# TinyISD1700_V2_2020-08-19-smd-sop-SPI-12.net
KiCad netlist of a schematic drawn in EAGLE
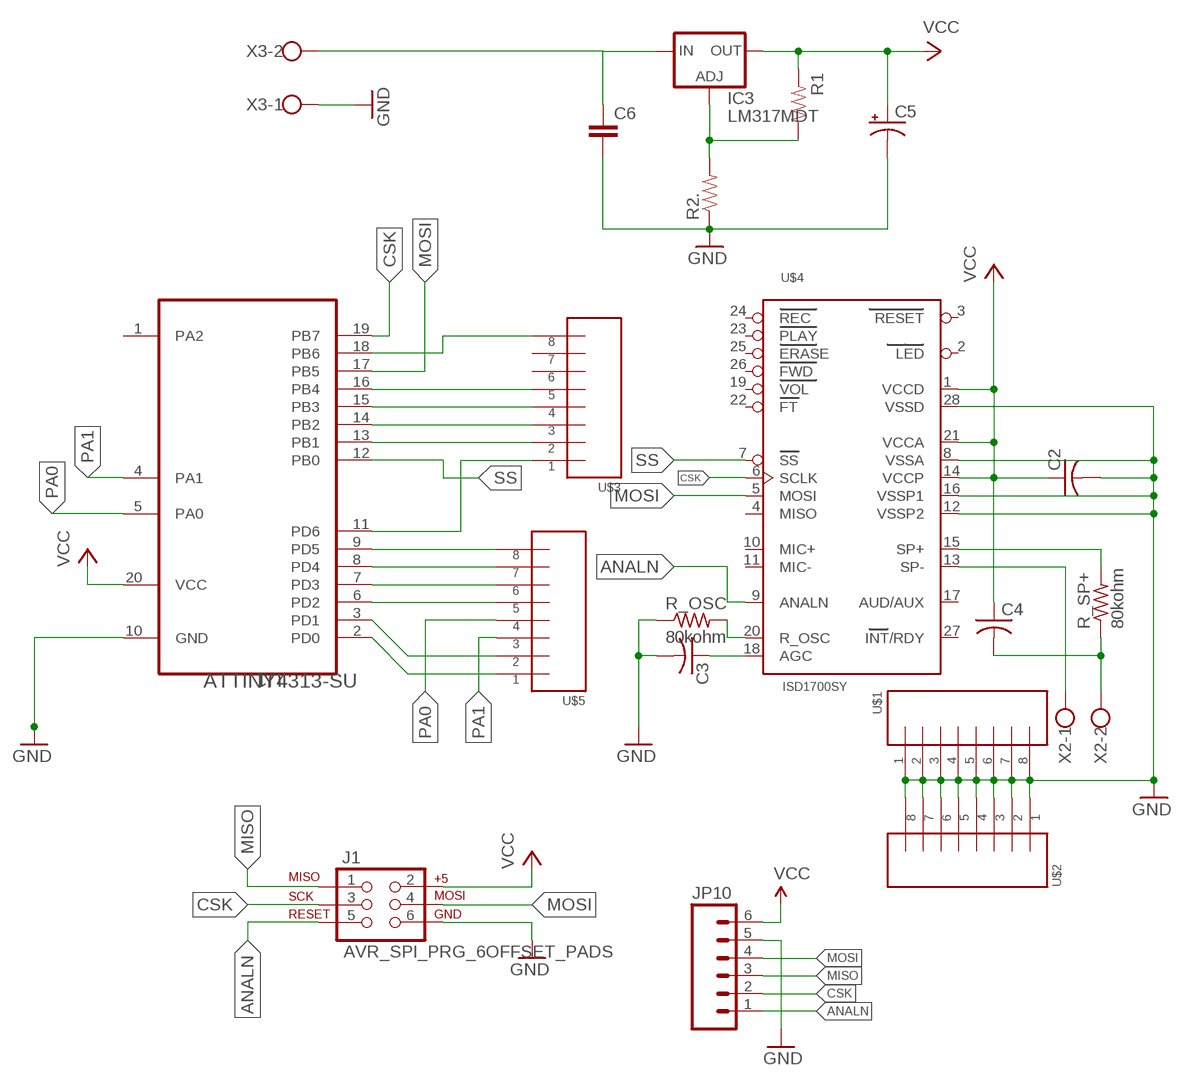
[diagram p0: schematic, sheet 1]

(export (version "E")
  (design (tool "Eeschema 10.0.6"))
  (components
    (comp (ref "C2")
      (value "C-US050-030X075")
      (footprint "eagle-import:C050-030X075")
      (libsource (lib "eagle-import") (part "C-US050-030X075"))
    )
    (comp (ref "C3")
      (value "C-US050-030X075")
      (footprint "eagle-import:C050-030X075")
      (libsource (lib "eagle-import") (part "C-US050-030X075"))
    )
    (comp (ref "C4")
      (value "C-US050-030X075")
      (footprint "eagle-import:C050-030X075")
      (libsource (lib "eagle-import") (part "C-US050-030X075"))
    )
    (comp (ref "C5")
      (value "CAP_POL1206")
      (footprint "eagle-import:EIA3216")
      (libsource (lib "eagle-import") (part "CAP_POL1206"))
    )
    (comp (ref "C6")
      (value "CAP0805")
      (footprint "eagle-import:0805")
      (libsource (lib "eagle-import") (part "CAP0805"))
    )
    (comp (ref "IC3")
      (value "LM317MDT")
      (footprint "eagle-import:DPACK")
      (libsource (lib "eagle-import") (part "LM317?MDT"))
    )
    (comp (ref "J1")
      (value "AVR_SPI_PRG_6OFFSET_PADS")
      (footprint "eagle-import:2X3_OFFSET")
      (libsource (lib "eagle-import") (part "AVR_SPI_PRG_6OFFSET_PADS"))
    )
    (comp (ref "JP10")
      (value "M06SIP")
      (footprint "eagle-import:1X06")
      (libsource (lib "eagle-import") (part "M06SIP"))
    )
    (comp (ref "R1")
      (value "RESISTOR")
      (footprint "eagle-import:0805")
      (libsource (lib "eagle-import") (part "RESISTOR"))
    )
    (comp (ref "R2.")
      (value "RESISTOR")
      (footprint "eagle-import:0805")
      (libsource (lib "eagle-import") (part "RESISTOR"))
    )
    (comp (ref "R_OSC")
      (value "80kohm")
      (footprint "eagle-import:0204V")
      (libsource (lib "eagle-import") (part "R-US_0204/2V"))
    )
    (comp (ref "R_SP+")
      (value "80kohm")
      (footprint "eagle-import:0204V")
      (libsource (lib "eagle-import") (part "R-US_0204/2V"))
    )
    (comp (ref "U$1")
      (value "8PIN_HEADER")
      (footprint "eagle-import:8PIN_HEADER")
      (fields (field (name "MF") "RENESAS") (field (name "MPN") "YSDKS128E10"))
      (libsource (lib "eagle-import") (part "8PIN_HEADER"))
    )
    (comp (ref "U$2")
      (value "8PIN_HEADER")
      (footprint "eagle-import:8PIN_HEADER")
      (fields (field (name "MF") "RENESAS") (field (name "MPN") "YSDKS128E10"))
      (libsource (lib "eagle-import") (part "8PIN_HEADER"))
    )
    (comp (ref "U$3")
      (value "8PIN_HEADER")
      (footprint "eagle-import:8PIN_HEADER")
      (fields (field (name "MF") "RENESAS") (field (name "MPN") "YSDKS128E10"))
      (libsource (lib "eagle-import") (part "8PIN_HEADER"))
    )
    (comp (ref "U$4")
      (value "ISD1700SY")
      (footprint "eagle-import:SO28W")
      (libsource (lib "eagle-import") (part "ISD1700SY"))
    )
    (comp (ref "U$5")
      (value "8PIN_HEADER")
      (footprint "eagle-import:8PIN_HEADER")
      (fields (field (name "MF") "RENESAS") (field (name "MPN") "YSDKS128E10"))
      (libsource (lib "eagle-import") (part "8PIN_HEADER"))
    )
    (comp (ref "U1")
      (value "ATTINY4313-SU")
      (footprint "eagle-import:SOIC127P1032X265-20N")
      (fields (field (name "MF") "MICROCHIP"))
      (libsource (lib "eagle-import") (part "ATTINY4313-SU"))
    )
    (comp (ref "X2")
      (value "W237-102")
      (footprint "eagle-import:W237-102")
      (fields (field (name "MPN") "237-102"))
      (libsource (lib "eagle-import") (part "W237-102"))
    )
    (comp (ref "X3")
      (value "W237-102")
      (footprint "eagle-import:W237-102")
      (fields (field (name "MPN") "237-102") (field (name "OC_NEWARK") "70K9898"))
      (libsource (lib "eagle-import") (part "W237-102"))
    )
  )
  (nets
    (net (code "1") (name "ANALN") (class "Default")
      (node (ref "J1") (pin "5") (pinfunction "5_5") (pintype "passive"))
      (node (ref "JP10") (pin "1") (pinfunction "1_1") (pintype "passive"))
      (node (ref "U$4") (pin "9") (pinfunction "ANALN_9") (pintype "input"))
    )
    (net (code "2") (name "CSK") (class "Default")
      (node (ref "J1") (pin "3") (pinfunction "3_3") (pintype "passive"))
      (node (ref "JP10") (pin "2") (pinfunction "2_2") (pintype "passive"))
      (node (ref "U$4") (pin "6") (pinfunction "SCLK_6") (pintype "input"))
      (node (ref "U1") (pin "19") (pinfunction "PB7_19") (pintype "bidirectional"))
    )
    (net (code "3") (name "GND") (class "Default")
      (node (ref "C2") (pin "2") (pinfunction "2_2") (pintype "passive"))
      (node (ref "C3") (pin "2") (pinfunction "2_2") (pintype "passive"))
      (node (ref "C5") (pin "C") (pinfunction "-_C") (pintype "passive"))
      (node (ref "C6") (pin "2") (pinfunction "2_2") (pintype "passive"))
      (node (ref "J1") (pin "6") (pinfunction "6_6") (pintype "passive"))
      (node (ref "JP10") (pin "5") (pinfunction "5_5") (pintype "passive"))
      (node (ref "R2.") (pin "1") (pinfunction "1_1") (pintype "passive"))
      (node (ref "R_OSC") (pin "1") (pinfunction "1_1") (pintype "passive"))
      (node (ref "U$1") (pin "P$1") (pinfunction "P$1_P$1") (pintype "bidirectional"))
      (node (ref "U$1") (pin "P$2") (pinfunction "P$2_P$2") (pintype "bidirectional"))
      (node (ref "U$1") (pin "P$3") (pinfunction "P$3_P$3") (pintype "bidirectional"))
      (node (ref "U$1") (pin "P$4") (pinfunction "P$4_P$4") (pintype "bidirectional"))
      (node (ref "U$1") (pin "P$5") (pinfunction "P$5_P$5") (pintype "bidirectional"))
      (node (ref "U$1") (pin "P$6") (pinfunction "P$6_P$6") (pintype "bidirectional"))
      (node (ref "U$1") (pin "P$7") (pinfunction "P$7_P$7") (pintype "bidirectional"))
      (node (ref "U$1") (pin "P$8") (pinfunction "P$8_P$8") (pintype "bidirectional"))
      (node (ref "U$2") (pin "P$1") (pinfunction "P$1_P$1") (pintype "bidirectional"))
      (node (ref "U$2") (pin "P$2") (pinfunction "P$2_P$2") (pintype "bidirectional"))
      (node (ref "U$2") (pin "P$3") (pinfunction "P$3_P$3") (pintype "bidirectional"))
      (node (ref "U$2") (pin "P$4") (pinfunction "P$4_P$4") (pintype "bidirectional"))
      (node (ref "U$2") (pin "P$5") (pinfunction "P$5_P$5") (pintype "bidirectional"))
      (node (ref "U$2") (pin "P$6") (pinfunction "P$6_P$6") (pintype "bidirectional"))
      (node (ref "U$2") (pin "P$7") (pinfunction "P$7_P$7") (pintype "bidirectional"))
      (node (ref "U$2") (pin "P$8") (pinfunction "P$8_P$8") (pintype "bidirectional"))
      (node (ref "U$4") (pin "12") (pinfunction "VSSP2_12") (pintype "power_in"))
      (node (ref "U$4") (pin "16") (pinfunction "VSSP1_16") (pintype "power_in"))
      (node (ref "U$4") (pin "28") (pinfunction "VSSD_28") (pintype "power_in"))
      (node (ref "U$4") (pin "8") (pinfunction "VSSA_8") (pintype "power_in"))
      (node (ref "U1") (pin "10") (pinfunction "GND_10") (pintype "passive"))
      (node (ref "X3") (pin "1") (pinfunction "KL_1") (pintype "passive"))
    )
    (net (code "4") (name "MISO") (class "Default")
      (node (ref "J1") (pin "1") (pinfunction "1_1") (pintype "passive"))
      (node (ref "JP10") (pin "3") (pinfunction "3_3") (pintype "passive"))
    )
    (net (code "5") (name "MOSI") (class "Default")
      (node (ref "J1") (pin "4") (pinfunction "4_4") (pintype "passive"))
      (node (ref "JP10") (pin "4") (pinfunction "4_4") (pintype "passive"))
      (node (ref "U$4") (pin "5") (pinfunction "MOSI_5") (pintype "input"))
      (node (ref "U1") (pin "17") (pinfunction "PB5_17") (pintype "bidirectional"))
    )
    (net (code "6") (name "Net-(IC3-ADJ)") (class "Default")
      (node (ref "IC3") (pin "1") (pinfunction "ADJ_1") (pintype "input"))
      (node (ref "R1") (pin "1") (pinfunction "1_1") (pintype "passive"))
      (node (ref "R2.") (pin "2") (pinfunction "2_2") (pintype "passive"))
    )
    (net (code "7") (name "Net-(IC3-IN)") (class "Default")
      (node (ref "C6") (pin "1") (pinfunction "1_1") (pintype "passive"))
      (node (ref "IC3") (pin "3") (pinfunction "IN_3") (pintype "input"))
      (node (ref "X3") (pin "2") (pinfunction "KL_2") (pintype "passive"))
    )
    (net (code "8") (name "Net-(U$4-AGC)") (class "Default")
      (node (ref "C3") (pin "1") (pinfunction "1_1") (pintype "passive"))
      (node (ref "U$4") (pin "18") (pinfunction "AGC_18") (pintype "passive"))
    )
    (net (code "9") (name "Net-(U$4-R_OSC)") (class "Default")
      (node (ref "R_OSC") (pin "2") (pinfunction "2_2") (pintype "passive"))
      (node (ref "U$4") (pin "20") (pinfunction "R_OSC_20") (pintype "passive"))
    )
    (net (code "10") (name "Net-(U$4-SP+)") (class "Default")
      (node (ref "R_SP+") (pin "2") (pinfunction "2_2") (pintype "passive"))
      (node (ref "U$4") (pin "15") (pinfunction "SP+_15") (pintype "output"))
    )
    (net (code "11") (name "Net-(U$4-SP-)") (class "Default")
      (node (ref "U$4") (pin "13") (pinfunction "SP-_13") (pintype "output"))
      (node (ref "X2") (pin "1") (pinfunction "KL_1") (pintype "passive"))
    )
    (net (code "12") (name "Net-(U1-PB1)") (class "Default")
      (node (ref "U$3") (pin "P$2") (pinfunction "P$2_P$2") (pintype "bidirectional"))
      (node (ref "U1") (pin "13") (pinfunction "PB1_13") (pintype "bidirectional"))
    )
    (net (code "13") (name "Net-(U1-PB2)") (class "Default")
      (node (ref "U$3") (pin "P$3") (pinfunction "P$3_P$3") (pintype "bidirectional"))
      (node (ref "U1") (pin "14") (pinfunction "PB2_14") (pintype "bidirectional"))
    )
    (net (code "14") (name "Net-(U1-PB3)") (class "Default")
      (node (ref "U$3") (pin "P$4") (pinfunction "P$4_P$4") (pintype "bidirectional"))
      (node (ref "U1") (pin "15") (pinfunction "PB3_15") (pintype "bidirectional"))
    )
    (net (code "15") (name "Net-(U1-PB4)") (class "Default")
      (node (ref "U$3") (pin "P$5") (pinfunction "P$5_P$5") (pintype "bidirectional"))
      (node (ref "U1") (pin "16") (pinfunction "PB4_16") (pintype "bidirectional"))
    )
    (net (code "16") (name "Net-(U1-PB6)") (class "Default")
      (node (ref "U$3") (pin "P$8") (pinfunction "P$8_P$8") (pintype "bidirectional"))
      (node (ref "U1") (pin "18") (pinfunction "PB6_18") (pintype "bidirectional"))
    )
    (net (code "17") (name "Net-(U1-PD0)") (class "Default")
      (node (ref "U$5") (pin "P$1") (pinfunction "P$1_P$1") (pintype "bidirectional"))
      (node (ref "U1") (pin "2") (pinfunction "PD0_2") (pintype "bidirectional"))
    )
    (net (code "18") (name "Net-(U1-PD1)") (class "Default")
      (node (ref "U$5") (pin "P$2") (pinfunction "P$2_P$2") (pintype "bidirectional"))
      (node (ref "U1") (pin "3") (pinfunction "PD1_3") (pintype "bidirectional"))
    )
    (net (code "19") (name "Net-(U1-PD2)") (class "Default")
      (node (ref "U$5") (pin "P$5") (pinfunction "P$5_P$5") (pintype "bidirectional"))
      (node (ref "U1") (pin "6") (pinfunction "PD2_6") (pintype "bidirectional"))
    )
    (net (code "20") (name "Net-(U1-PD3)") (class "Default")
      (node (ref "U$5") (pin "P$6") (pinfunction "P$6_P$6") (pintype "bidirectional"))
      (node (ref "U1") (pin "7") (pinfunction "PD3_7") (pintype "bidirectional"))
    )
    (net (code "21") (name "Net-(U1-PD4)") (class "Default")
      (node (ref "U$5") (pin "P$7") (pinfunction "P$7_P$7") (pintype "bidirectional"))
      (node (ref "U1") (pin "8") (pinfunction "PD4_8") (pintype "bidirectional"))
    )
    (net (code "22") (name "Net-(U1-PD5)") (class "Default")
      (node (ref "U$5") (pin "P$8") (pinfunction "P$8_P$8") (pintype "bidirectional"))
      (node (ref "U1") (pin "9") (pinfunction "PD5_9") (pintype "bidirectional"))
    )
    (net (code "23") (name "Net-(U1-PD6)") (class "Default")
      (node (ref "U$3") (pin "P$1") (pinfunction "P$1_P$1") (pintype "bidirectional"))
      (node (ref "U1") (pin "11") (pinfunction "PD6_11") (pintype "bidirectional"))
    )
    (net (code "24") (name "Net-(X2B-KL)") (class "Default")
      (node (ref "C4") (pin "2") (pinfunction "2_2") (pintype "passive"))
      (node (ref "R_SP+") (pin "1") (pinfunction "1_1") (pintype "passive"))
      (node (ref "X2") (pin "2") (pinfunction "KL_2") (pintype "passive"))
    )
    (net (code "25") (name "PA0") (class "Default")
      (node (ref "U$5") (pin "P$4") (pinfunction "P$4_P$4") (pintype "bidirectional"))
      (node (ref "U1") (pin "5") (pinfunction "PA0_5") (pintype "bidirectional"))
    )
    (net (code "26") (name "PA1") (class "Default")
      (node (ref "U$5") (pin "P$3") (pinfunction "P$3_P$3") (pintype "bidirectional"))
      (node (ref "U1") (pin "4") (pinfunction "PA1_4") (pintype "bidirectional"))
    )
    (net (code "27") (name "SS") (class "Default")
      (node (ref "U$4") (pin "7") (pinfunction "SS_7") (pintype "input"))
      (node (ref "U1") (pin "12") (pinfunction "PB0_12") (pintype "bidirectional"))
    )
    (net (code "28") (name "VCC") (class "Default")
      (node (ref "C2") (pin "1") (pinfunction "1_1") (pintype "passive"))
      (node (ref "C4") (pin "1") (pinfunction "1_1") (pintype "passive"))
      (node (ref "C5") (pin "A") (pinfunction "+_A") (pintype "passive"))
      (node (ref "IC3") (pin "4") (pinfunction "OUT_4") (pintype "passive"))
      (node (ref "J1") (pin "2") (pinfunction "2_2") (pintype "passive"))
      (node (ref "JP10") (pin "6") (pinfunction "6_6") (pintype "passive"))
      (node (ref "R1") (pin "2") (pinfunction "2_2") (pintype "passive"))
      (node (ref "U$4") (pin "1") (pinfunction "VCCD_1") (pintype "power_in"))
      (node (ref "U$4") (pin "14") (pinfunction "VCCP_14") (pintype "power_in"))
      (node (ref "U$4") (pin "21") (pinfunction "VCCA_21") (pintype "power_in"))
      (node (ref "U1") (pin "20") (pinfunction "VCC_20") (pintype "power_in"))
    )
    (net (code "29") (name "unconnected-(U$3-PadP$6)") (class "Default")
      (node (ref "U$3") (pin "P$6") (pinfunction "P$6_P$6") (pintype "bidirectional"))
    )
    (net (code "30") (name "unconnected-(U$3-PadP$7)") (class "Default")
      (node (ref "U$3") (pin "P$7") (pinfunction "P$7_P$7") (pintype "bidirectional"))
    )
    (net (code "31") (name "unconnected-(U$4-AUD{slash}AUX-Pad17)") (class "Default")
      (node (ref "U$4") (pin "17") (pinfunction "AUD/AUX_17") (pintype "output"))
    )
    (net (code "32") (name "unconnected-(U$4-ERASE-Pad25)") (class "Default")
      (node (ref "U$4") (pin "25") (pinfunction "ERASE_25") (pintype "input"))
    )
    (net (code "33") (name "unconnected-(U$4-FT-Pad22)") (class "Default")
      (node (ref "U$4") (pin "22") (pinfunction "FT_22") (pintype "input"))
    )
    (net (code "34") (name "unconnected-(U$4-FWD-Pad26)") (class "Default")
      (node (ref "U$4") (pin "26") (pinfunction "FWD_26") (pintype "input"))
    )
    (net (code "35") (name "unconnected-(U$4-INT{slash}RDY-Pad27)") (class "Default")
      (node (ref "U$4") (pin "27") (pinfunction "INT/RDY_27") (pintype "bidirectional"))
    )
    (net (code "36") (name "unconnected-(U$4-LED-Pad2)") (class "Default")
      (node (ref "U$4") (pin "2") (pinfunction "LED_2") (pintype "input"))
    )
    (net (code "37") (name "unconnected-(U$4-MIC+-Pad10)") (class "Default")
      (node (ref "U$4") (pin "10") (pinfunction "MIC+_10") (pintype "input"))
    )
    (net (code "38") (name "unconnected-(U$4-MIC--Pad11)") (class "Default")
      (node (ref "U$4") (pin "11") (pinfunction "MIC-_11") (pintype "input"))
    )
    (net (code "39") (name "unconnected-(U$4-MISO-Pad4)") (class "Default")
      (node (ref "U$4") (pin "4") (pinfunction "MISO_4") (pintype "input"))
    )
    (net (code "40") (name "unconnected-(U$4-PLAY-Pad23)") (class "Default")
      (node (ref "U$4") (pin "23") (pinfunction "PLAY_23") (pintype "input"))
    )
    (net (code "41") (name "unconnected-(U$4-REC-Pad24)") (class "Default")
      (node (ref "U$4") (pin "24") (pinfunction "REC_24") (pintype "input"))
    )
    (net (code "42") (name "unconnected-(U$4-RESET-Pad3)") (class "Default")
      (node (ref "U$4") (pin "3") (pinfunction "RESET_3") (pintype "input"))
    )
    (net (code "43") (name "unconnected-(U$4-VOL-Pad19)") (class "Default")
      (node (ref "U$4") (pin "19") (pinfunction "VOL_19") (pintype "input"))
    )
    (net (code "44") (name "unconnected-(U1-PA2-Pad1)") (class "Default")
      (node (ref "U1") (pin "1") (pinfunction "PA2_1") (pintype "bidirectional"))
    )
  )
)
